# 3_STM32_Tutorial-Peripheral.net
KiCad netlist of a schematic drawn in Altium Designer
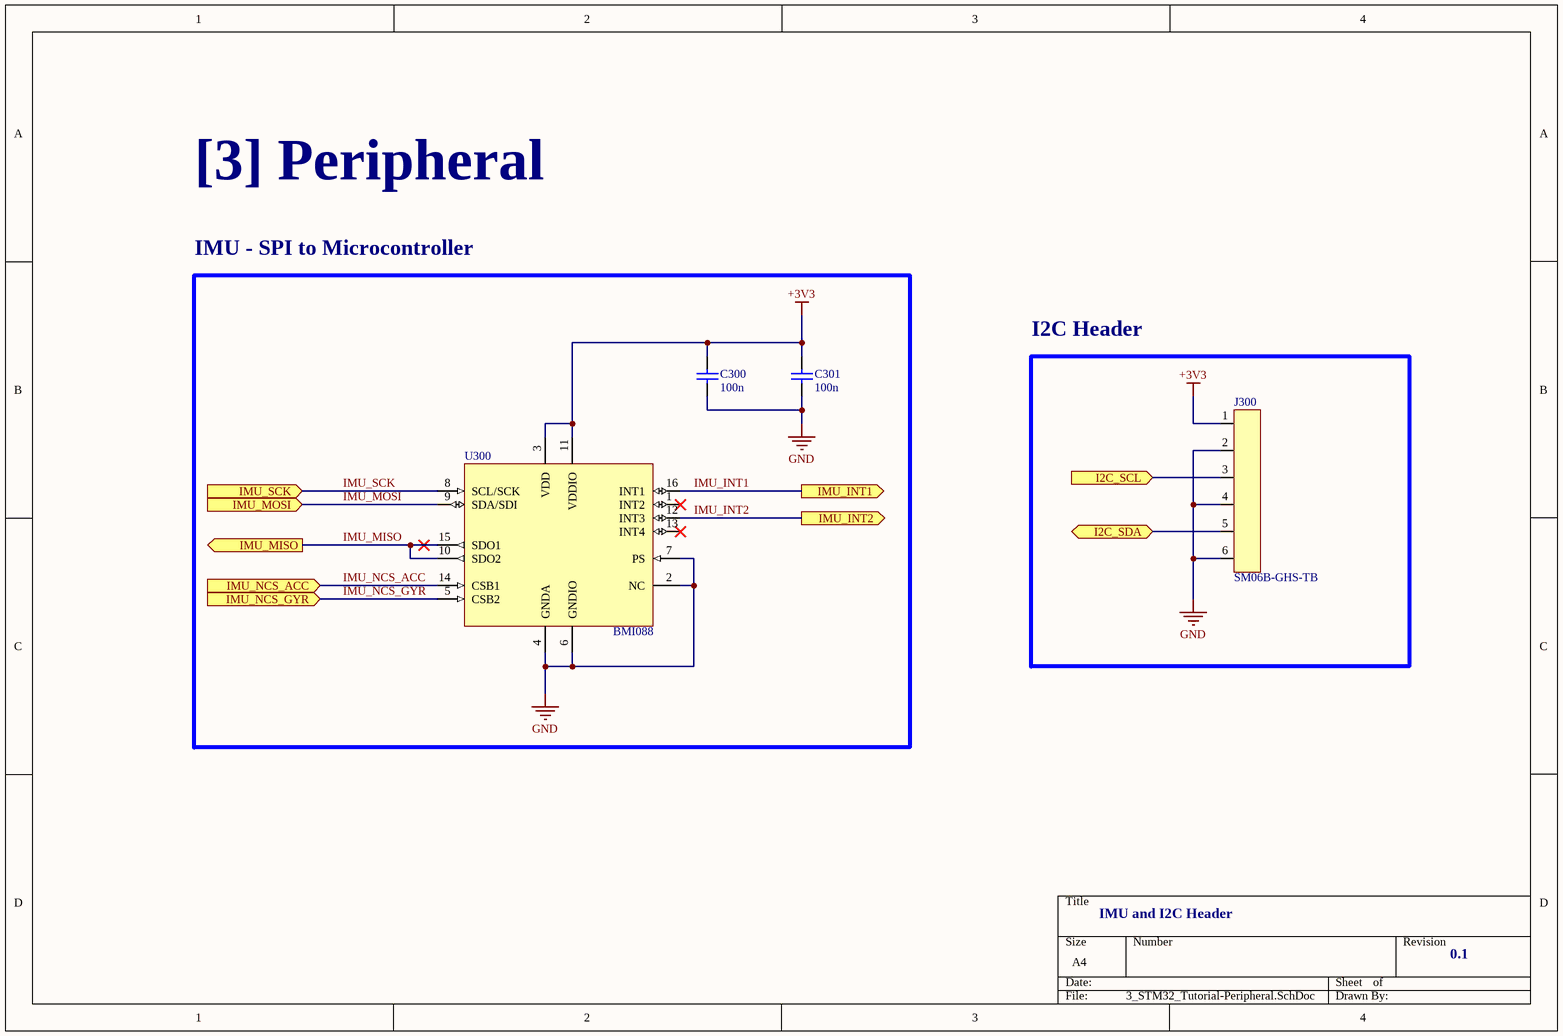
[diagram p0: 3_STM32_Tutorial-Peripheral.SchDoc]

(export (version "E")
  (design (tool "Eeschema 10.0.6"))
  (components
    (comp (ref "C300")
      (value "100n")
      (footprint "CAP_0603")
      (description "Capacitor SMD 0603 Generic")
      (libsource (lib "AndreiLib") (part "CAP_0603"))
    )
    (comp (ref "C301")
      (value "100n")
      (footprint "CAP_0603")
      (description "Capacitor SMD 0603 Generic")
      (libsource (lib "AndreiLib") (part "CAP_0603"))
    )
    (comp (ref "J300")
      (value "SM06B-GHS-TB")
      (footprint "SM06B-GHS-TB")
      (description "Header Connector 6 Position 1.25MM Pitch SMD Horizontal JST GH")
      (libsource (lib "AndreiLib") (part "SM06B-GHS-TB"))
    )
    (comp (ref "U300")
      (value "BMI088")
      (footprint "BMI088")
      (description "Inertial Measurement Unit IMU 6-Axis LGA")
      (fields (field (name "MANUFACTURER") "Bosch"))
      (libsource (lib "AndreiLib") (part "BMI088"))
    )
  )
  (nets
    (net (code "1") (name "+3V3") (class "Default")
      (node (ref "C300") (pin "2") (pintype "passive"))
      (node (ref "C301") (pin "2") (pintype "passive"))
      (node (ref "J300") (pin "1") (pinfunction "1_1") (pintype "passive"))
      (node (ref "U300") (pin "11") (pinfunction "VDDIO_11") (pintype "power_in"))
      (node (ref "U300") (pin "3") (pinfunction "VDD_3") (pintype "power_in"))
    )
    (net (code "2") (name "/I2C_SCL") (class "Default")
      (node (ref "J300") (pin "3") (pinfunction "3_3") (pintype "passive"))
    )
    (net (code "3") (name "/I2C_SDA") (class "Default")
      (node (ref "J300") (pin "5") (pinfunction "5_5") (pintype "passive"))
    )
    (net (code "4") (name "/IMU_INT1") (class "Default")
      (node (ref "U300") (pin "16") (pinfunction "INT1_16") (pintype "bidirectional"))
    )
    (net (code "5") (name "/IMU_INT2") (class "Default")
      (node (ref "U300") (pin "12") (pinfunction "INT3_12") (pintype "bidirectional"))
    )
    (net (code "6") (name "/IMU_MISO") (class "Default")
      (node (ref "U300") (pin "10") (pinfunction "SDO2_10") (pintype "output"))
      (node (ref "U300") (pin "15") (pinfunction "SDO1_15") (pintype "output"))
    )
    (net (code "7") (name "/IMU_MOSI") (class "Default")
      (node (ref "U300") (pin "9") (pinfunction "SDA/SDI_9") (pintype "bidirectional"))
    )
    (net (code "8") (name "/IMU_NCS_ACC") (class "Default")
      (node (ref "U300") (pin "14") (pinfunction "CSB1_14") (pintype "input"))
    )
    (net (code "9") (name "/IMU_NCS_GYR") (class "Default")
      (node (ref "U300") (pin "5") (pinfunction "CSB2_5") (pintype "input"))
    )
    (net (code "10") (name "/IMU_SCK") (class "Default")
      (node (ref "U300") (pin "8") (pinfunction "SCL/SCK_8") (pintype "input"))
    )
    (net (code "11") (name "GND") (class "Default")
      (node (ref "C300") (pin "1") (pintype "passive"))
      (node (ref "C301") (pin "1") (pintype "passive"))
      (node (ref "J300") (pin "2") (pinfunction "2_2") (pintype "passive"))
      (node (ref "J300") (pin "4") (pinfunction "4_4") (pintype "passive"))
      (node (ref "J300") (pin "6") (pinfunction "6_6") (pintype "passive"))
      (node (ref "U300") (pin "2") (pinfunction "NC_2") (pintype "passive"))
      (node (ref "U300") (pin "4") (pinfunction "GNDA_4") (pintype "power_in"))
      (node (ref "U300") (pin "6") (pinfunction "GNDIO_6") (pintype "power_in"))
      (node (ref "U300") (pin "7") (pinfunction "PS_7") (pintype "input"))
    )
    (net (code "12") (name "unconnected-(U300-INT2-Pad1)") (class "Default")
      (node (ref "U300") (pin "1") (pinfunction "INT2_1") (pintype "bidirectional+no_connect"))
    )
    (net (code "13") (name "unconnected-(U300-INT4-Pad13)") (class "Default")
      (node (ref "U300") (pin "13") (pinfunction "INT4_13") (pintype "bidirectional+no_connect"))
    )
  )
)
